# 3_-Digital_Input.net
KiCad netlist of a schematic drawn in Altium Designer
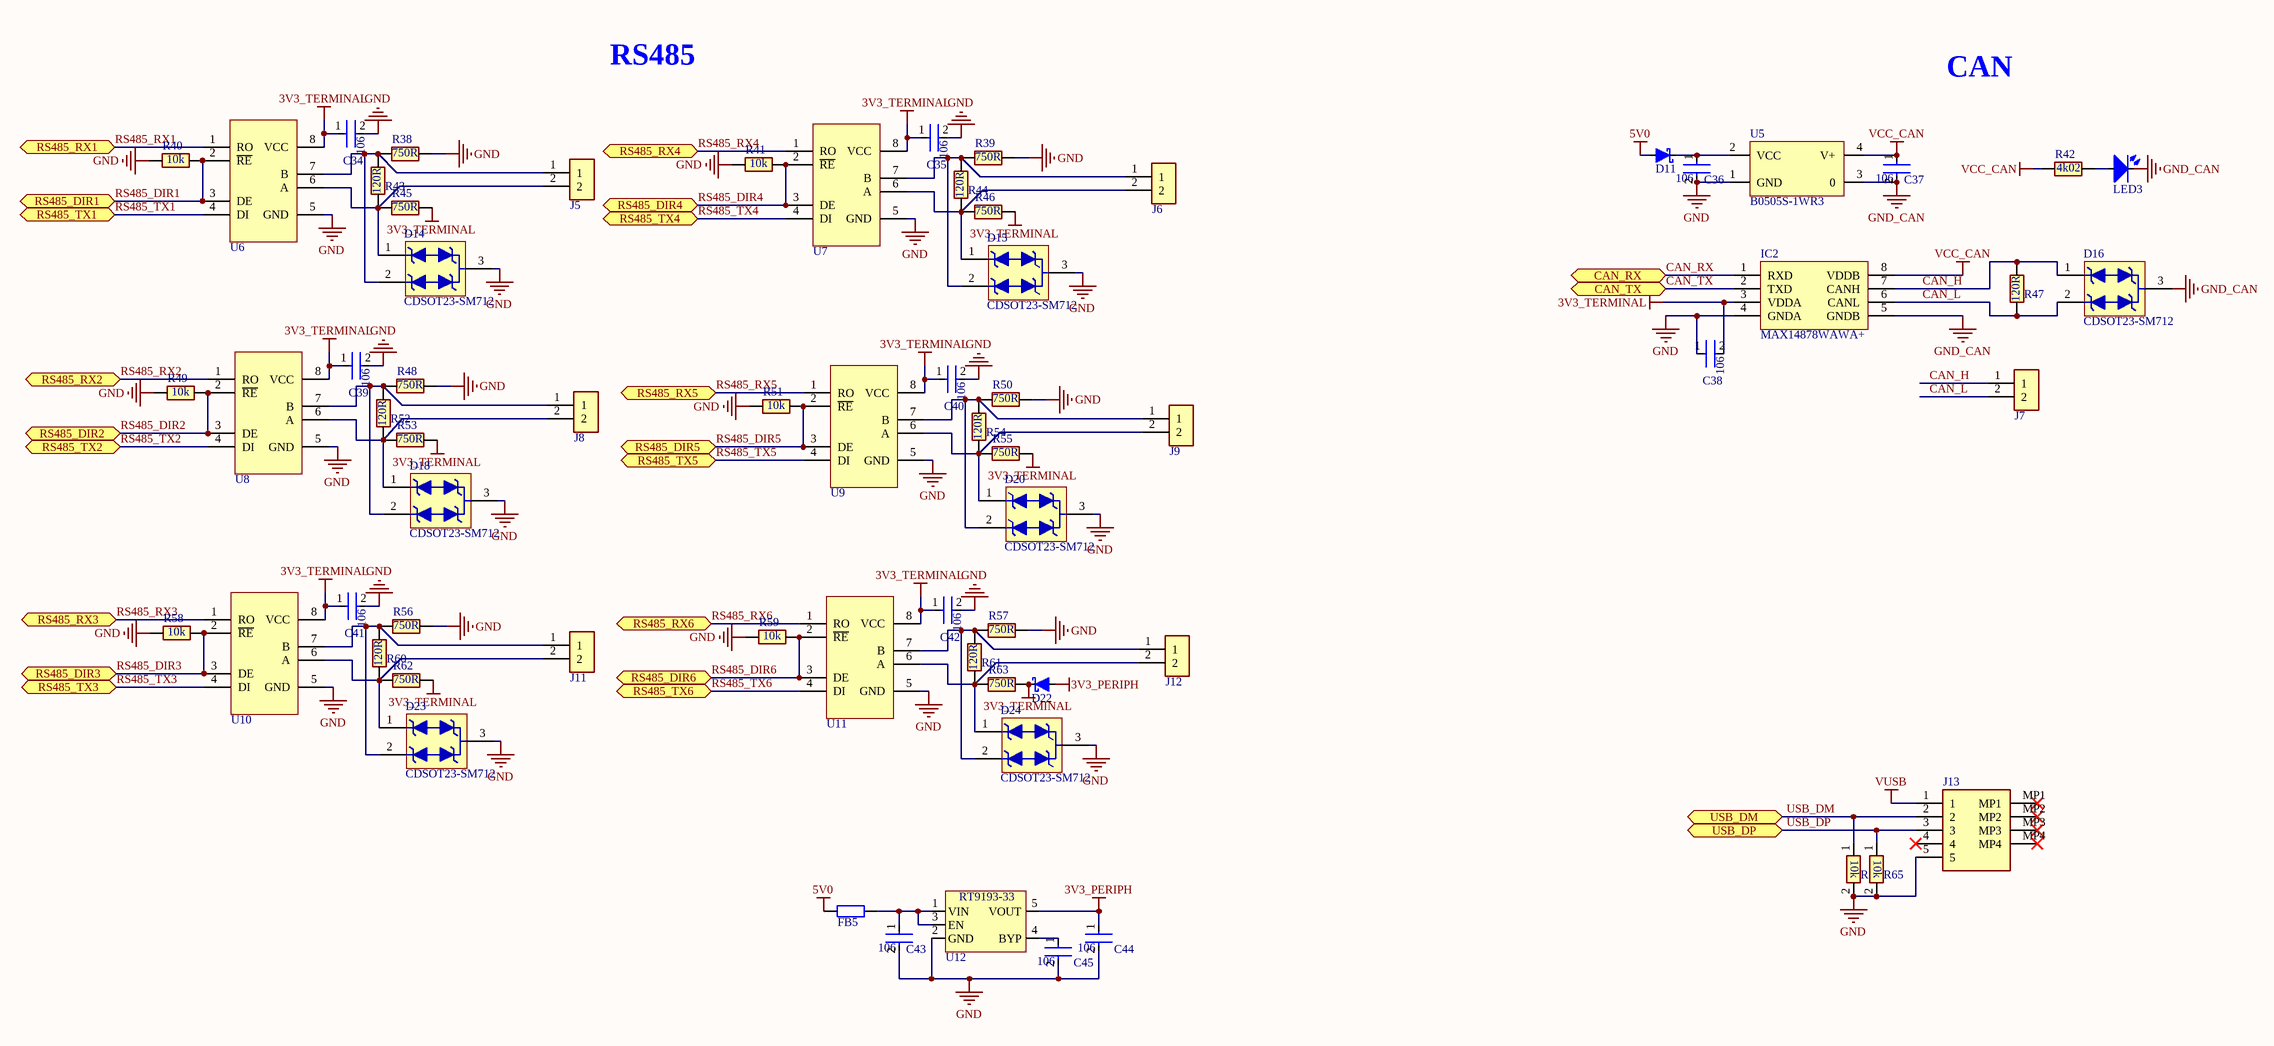
[diagram p0: [3]-Digital Input.SchDoc]

(export (version "E")
  (design (tool "Eeschema 10.0.6"))
  (components
    (comp (ref "C34")
      (value "C0603_106_35V")
      (footprint "SamacSys:C0603")
      (description "Multilayer Ceramic Capacitors MLCC - SMD/SMT 10 uF 35 VDC 20% 0603 X5R")
      (fields
        (field (name "MANUFACTURER_PART_NUMBER") "GRM188R6YA106MA73J")
        (field (name "MOUSER PART NUMBER") "81-GRM188R6YA106MA3J")
      )
      (libsource (lib "SamacSys") (part "C0603_106_35V"))
    )
    (comp (ref "C35")
      (value "C0603_106_35V")
      (footprint "SamacSys:C0603")
      (description "Multilayer Ceramic Capacitors MLCC - SMD/SMT 10 uF 35 VDC 20% 0603 X5R")
      (fields
        (field (name "MANUFACTURER_PART_NUMBER") "GRM188R6YA106MA73J")
        (field (name "MOUSER PART NUMBER") "81-GRM188R6YA106MA3J")
      )
      (libsource (lib "SamacSys") (part "C0603_106_35V"))
    )
    (comp (ref "C36")
      (value "C0603_106_35V")
      (footprint "SamacSys:C0603")
      (description "Multilayer Ceramic Capacitors MLCC - SMD/SMT 10 uF 35 VDC 20% 0603 X5R")
      (fields
        (field (name "MANUFACTURER_PART_NUMBER") "GRM188R6YA106MA73J")
        (field (name "MOUSER PART NUMBER") "81-GRM188R6YA106MA3J")
      )
      (libsource (lib "SamacSys") (part "C0603_106_35V"))
    )
    (comp (ref "C37")
      (value "C0603_106_35V")
      (footprint "SamacSys:C0603")
      (description "Multilayer Ceramic Capacitors MLCC - SMD/SMT 10 uF 35 VDC 20% 0603 X5R")
      (fields
        (field (name "MANUFACTURER_PART_NUMBER") "GRM188R6YA106MA73J")
        (field (name "MOUSER PART NUMBER") "81-GRM188R6YA106MA3J")
      )
      (libsource (lib "SamacSys") (part "C0603_106_35V"))
    )
    (comp (ref "C38")
      (value "C0603_106_35V")
      (footprint "SamacSys:C0603")
      (description "Multilayer Ceramic Capacitors MLCC - SMD/SMT 10 uF 35 VDC 20% 0603 X5R")
      (fields
        (field (name "MANUFACTURER_PART_NUMBER") "GRM188R6YA106MA73J")
        (field (name "MOUSER PART NUMBER") "81-GRM188R6YA106MA3J")
      )
      (libsource (lib "SamacSys") (part "C0603_106_35V"))
    )
    (comp (ref "C39")
      (value "C0603_106_35V")
      (footprint "SamacSys:C0603")
      (description "Multilayer Ceramic Capacitors MLCC - SMD/SMT 10 uF 35 VDC 20% 0603 X5R")
      (fields
        (field (name "MANUFACTURER_PART_NUMBER") "GRM188R6YA106MA73J")
        (field (name "MOUSER PART NUMBER") "81-GRM188R6YA106MA3J")
      )
      (libsource (lib "SamacSys") (part "C0603_106_35V"))
    )
    (comp (ref "C40")
      (value "C0603_106_35V")
      (footprint "SamacSys:C0603")
      (description "Multilayer Ceramic Capacitors MLCC - SMD/SMT 10 uF 35 VDC 20% 0603 X5R")
      (fields
        (field (name "MANUFACTURER_PART_NUMBER") "GRM188R6YA106MA73J")
        (field (name "MOUSER PART NUMBER") "81-GRM188R6YA106MA3J")
      )
      (libsource (lib "SamacSys") (part "C0603_106_35V"))
    )
    (comp (ref "C41")
      (value "C0603_106_35V")
      (footprint "SamacSys:C0603")
      (description "Multilayer Ceramic Capacitors MLCC - SMD/SMT 10 uF 35 VDC 20% 0603 X5R")
      (fields
        (field (name "MANUFACTURER_PART_NUMBER") "GRM188R6YA106MA73J")
        (field (name "MOUSER PART NUMBER") "81-GRM188R6YA106MA3J")
      )
      (libsource (lib "SamacSys") (part "C0603_106_35V"))
    )
    (comp (ref "C42")
      (value "C0603_106_35V")
      (footprint "SamacSys:C0603")
      (description "Multilayer Ceramic Capacitors MLCC - SMD/SMT 10 uF 35 VDC 20% 0603 X5R")
      (fields
        (field (name "MANUFACTURER_PART_NUMBER") "GRM188R6YA106MA73J")
        (field (name "MOUSER PART NUMBER") "81-GRM188R6YA106MA3J")
      )
      (libsource (lib "SamacSys") (part "C0603_106_35V"))
    )
    (comp (ref "C43")
      (value "C0603_106_35V")
      (footprint "SamacSys:C0603")
      (description "Multilayer Ceramic Capacitors MLCC - SMD/SMT 10 uF 35 VDC 20% 0603 X5R")
      (fields
        (field (name "MANUFACTURER_PART_NUMBER") "GRM188R6YA106MA73J")
        (field (name "MOUSER PART NUMBER") "81-GRM188R6YA106MA3J")
      )
      (libsource (lib "SamacSys") (part "C0603_106_35V"))
    )
    (comp (ref "C44")
      (value "C0603_106_35V")
      (footprint "SamacSys:C0603")
      (description "Multilayer Ceramic Capacitors MLCC - SMD/SMT 10 uF 35 VDC 20% 0603 X5R")
      (fields
        (field (name "MANUFACTURER_PART_NUMBER") "GRM188R6YA106MA73J")
        (field (name "MOUSER PART NUMBER") "81-GRM188R6YA106MA3J")
      )
      (libsource (lib "SamacSys") (part "C0603_106_35V"))
    )
    (comp (ref "C45")
      (value "C0603_106_35V")
      (footprint "SamacSys:C0603")
      (description "Multilayer Ceramic Capacitors MLCC - SMD/SMT 10 uF 35 VDC 20% 0603 X5R")
      (fields
        (field (name "MANUFACTURER_PART_NUMBER") "GRM188R6YA106MA73J")
        (field (name "MOUSER PART NUMBER") "81-GRM188R6YA106MA3J")
      )
      (libsource (lib "SamacSys") (part "C0603_106_35V"))
    )
    (comp (ref "D11")
      (value "PMEG40T30ERX")
      (footprint "SamacSys:SOD123")
      (description "Schottky Diode 40V 3A")
      (fields (field (name "MOUSER PART NUMBER") "771-PMEG40T30ERX"))
      (libsource (lib "SamacSys") (part "PMEG40T30ERX"))
    )
    (comp (ref "D14")
      (value "CDSOT23-SM712")
      (footprint "SamacSys:SOT-23")
      (fields (field (name "MANUFACTURER") "Bourns Inc."))
      (libsource (lib "SamacSys") (part "CDSOT23-SM712"))
    )
    (comp (ref "D15")
      (value "CDSOT23-SM712")
      (footprint "SamacSys:SOT-23")
      (fields (field (name "MANUFACTURER") "Bourns Inc."))
      (libsource (lib "SamacSys") (part "CDSOT23-SM712"))
    )
    (comp (ref "D16")
      (value "CDSOT23-SM712")
      (footprint "SamacSys:SOT-23")
      (fields (field (name "MANUFACTURER") "Bourns Inc."))
      (libsource (lib "SamacSys") (part "CDSOT23-SM712"))
    )
    (comp (ref "D18")
      (value "CDSOT23-SM712")
      (footprint "SamacSys:SOT-23")
      (fields (field (name "MANUFACTURER") "Bourns Inc."))
      (libsource (lib "SamacSys") (part "CDSOT23-SM712"))
    )
    (comp (ref "D20")
      (value "CDSOT23-SM712")
      (footprint "SamacSys:SOT-23")
      (fields (field (name "MANUFACTURER") "Bourns Inc."))
      (libsource (lib "SamacSys") (part "CDSOT23-SM712"))
    )
    (comp (ref "D22")
      (value "PMEG40T30ERX")
      (footprint "SamacSys:SOD123")
      (description "Schottky Diode 40V 3A")
      (fields (field (name "MOUSER PART NUMBER") "771-PMEG40T30ERX"))
      (libsource (lib "SamacSys") (part "PMEG40T30ERX"))
    )
    (comp (ref "D23")
      (value "CDSOT23-SM712")
      (footprint "SamacSys:SOT-23")
      (fields (field (name "MANUFACTURER") "Bourns Inc."))
      (libsource (lib "SamacSys") (part "CDSOT23-SM712"))
    )
    (comp (ref "D24")
      (value "CDSOT23-SM712")
      (footprint "SamacSys:SOT-23")
      (fields (field (name "MANUFACTURER") "Bourns Inc."))
      (libsource (lib "SamacSys") (part "CDSOT23-SM712"))
    )
    (comp (ref "FB5")
      (value "FERRIT_0805_1A")
      (footprint "SamacSys:FB0805")
      (fields
        (field (name "MANUFACTURER") "Laird-Signal Integrity Products")
        (field (name "PART NUMBER") "MI0805J102R-10")
      )
      (libsource (lib "SamacSys") (part "FERRIT_0805_1A"))
    )
    (comp (ref "IC2")
      (value "MAX14878WAWA+")
      (footprint "SamacSys:8-SOIC-W")
      (description "Integrated Circuit")
      (fields (field (name "MOUSER PART NUMBER") "700-MAX14878WAWA+"))
      (libsource (lib "SamacSys") (part "MAX14878WAWA+"))
    )
    (comp (ref "J5")
      (value "Terminal_2P_5.08mm")
      (footprint "SamacSys:1729128")
      (description "Fixed Terminal Blocks 2P 5.08mm 90DEG")
      (fields
        (field (name "MANUFACTURER_PART_NUMBER") "1729128")
        (field (name "MOUSER PART NUMBER") "651-1729128")
      )
      (libsource (lib "SamacSys") (part "Terminal_2P_5.08mm"))
    )
    (comp (ref "J6")
      (value "Terminal_2P_5.08mm")
      (footprint "SamacSys:1729128")
      (description "Fixed Terminal Blocks 2P 5.08mm 90DEG")
      (fields
        (field (name "MANUFACTURER_PART_NUMBER") "1729128")
        (field (name "MOUSER PART NUMBER") "651-1729128")
      )
      (libsource (lib "SamacSys") (part "Terminal_2P_5.08mm"))
    )
    (comp (ref "J7")
      (value "Terminal_2P_5.08mm")
      (footprint "SamacSys:1729128")
      (description "Fixed Terminal Blocks 2P 5.08mm 90DEG")
      (fields
        (field (name "MANUFACTURER_PART_NUMBER") "1729128")
        (field (name "MOUSER PART NUMBER") "651-1729128")
      )
      (libsource (lib "SamacSys") (part "Terminal_2P_5.08mm"))
    )
    (comp (ref "J8")
      (value "Terminal_2P_5.08mm")
      (footprint "SamacSys:1729128")
      (description "Fixed Terminal Blocks 2P 5.08mm 90DEG")
      (fields
        (field (name "MANUFACTURER_PART_NUMBER") "1729128")
        (field (name "MOUSER PART NUMBER") "651-1729128")
      )
      (libsource (lib "SamacSys") (part "Terminal_2P_5.08mm"))
    )
    (comp (ref "J9")
      (value "Terminal_2P_5.08mm")
      (footprint "SamacSys:1729128")
      (description "Fixed Terminal Blocks 2P 5.08mm 90DEG")
      (fields
        (field (name "MANUFACTURER_PART_NUMBER") "1729128")
        (field (name "MOUSER PART NUMBER") "651-1729128")
      )
      (libsource (lib "SamacSys") (part "Terminal_2P_5.08mm"))
    )
    (comp (ref "J11")
      (value "Terminal_2P_5.08mm")
      (footprint "SamacSys:1729128")
      (description "Fixed Terminal Blocks 2P 5.08mm 90DEG")
      (fields
        (field (name "MANUFACTURER_PART_NUMBER") "1729128")
        (field (name "MOUSER PART NUMBER") "651-1729128")
      )
      (libsource (lib "SamacSys") (part "Terminal_2P_5.08mm"))
    )
    (comp (ref "J12")
      (value "Terminal_2P_5.08mm")
      (footprint "SamacSys:1729128")
      (description "Fixed Terminal Blocks 2P 5.08mm 90DEG")
      (fields
        (field (name "MANUFACTURER_PART_NUMBER") "1729128")
        (field (name "MOUSER PART NUMBER") "651-1729128")
      )
      (libsource (lib "SamacSys") (part "Terminal_2P_5.08mm"))
    )
    (comp (ref "J13")
      (value "1734035-3")
      (footprint "17340353")
      (description "Connector")
      (fields (field (name "MOUSER PART NUMBER") "571-1734035-3"))
      (libsource (lib "SamacSys") (part "1734035-3"))
    )
    (comp (ref "LED3")
      (value "LED0603_Blue")
      (footprint "SamacSys:LED0603")
      (description "Blue 470nm LED Indication - Discrete 3.2V 0603 (1608 Metric)")
      (fields
        (field (name "MANUFACTURER_PART_NUMBER") "150060BS75000")
        (field (name "MOUSER PART NUMBER") "710-150060BS75000")
      )
      (libsource (lib "SamacSys") (part "LED0603_Blue"))
    )
    (comp (ref "R38")
      (value "R0603_750R")
      (footprint "SamacSys:RES-SMD-0603")
      (description "Resistor")
      (fields
        (field (name "MANUFACTURER_PART_NUMBER") "ERJ-3EKF7500V")
        (field (name "MOUSER PART NUMBER") "667-ERJ-3EKF7500V")
      )
      (libsource (lib "SamacSys") (part "R0603_750R"))
    )
    (comp (ref "R39")
      (value "R0603_750R")
      (footprint "SamacSys:RES-SMD-0603")
      (description "Resistor")
      (fields
        (field (name "MANUFACTURER_PART_NUMBER") "ERJ-3EKF7500V")
        (field (name "MOUSER PART NUMBER") "667-ERJ-3EKF7500V")
      )
      (libsource (lib "SamacSys") (part "R0603_750R"))
    )
    (comp (ref "R40")
      (value "R0603_10k")
      (footprint "SamacSys:RES-SMD-0603")
      (description "Thick Film Resistors - SMD 0603 10Kohms 1% AEC-Q200")
      (fields
        (field (name "MANUFACTURER_PART_NUMBER") "ERJ-3EKF1002V")
        (field (name "MOUSER PART NUMBER") "667-ERJ-3EKF1002V")
      )
      (libsource (lib "SamacSys") (part "R0603_10k"))
    )
    (comp (ref "R41")
      (value "R0603_10k")
      (footprint "SamacSys:RES-SMD-0603")
      (description "Thick Film Resistors - SMD 0603 10Kohms 1% AEC-Q200")
      (fields
        (field (name "MANUFACTURER_PART_NUMBER") "ERJ-3EKF1002V")
        (field (name "MOUSER PART NUMBER") "667-ERJ-3EKF1002V")
      )
      (libsource (lib "SamacSys") (part "R0603_10k"))
    )
    (comp (ref "R42")
      (value "R0603_4k02")
      (footprint "SamacSys:RES-SMD-0603")
      (description "Resistor")
      (fields
        (field (name "MANUFACTURER_PART_NUMBER") "ERJ-3EKF4021V")
        (field (name "MOUSER PART NUMBER") "667-ERJ-3EKF4021V")
      )
      (libsource (lib "SamacSys") (part "R0603_4k02"))
    )
    (comp (ref "R43")
      (value "R0603_120R")
      (footprint "SamacSys:RES-SMD-0603")
      (description "Thick Film Resistors - SMD 0603 120ohms 1% AEC-Q200")
      (fields
        (field (name "MANUFACTURER_PART_NUMBER") "ERJ-3EKF1200V")
        (field (name "MOUSER PART NUMBER") "667-ERJ-3EKF1200V")
      )
      (libsource (lib "SamacSys") (part "R0603_120R"))
    )
    (comp (ref "R44")
      (value "R0603_120R")
      (footprint "SamacSys:RES-SMD-0603")
      (description "Thick Film Resistors - SMD 0603 120ohms 1% AEC-Q200")
      (fields
        (field (name "MANUFACTURER_PART_NUMBER") "ERJ-3EKF1200V")
        (field (name "MOUSER PART NUMBER") "667-ERJ-3EKF1200V")
      )
      (libsource (lib "SamacSys") (part "R0603_120R"))
    )
    (comp (ref "R45")
      (value "R0603_750R")
      (footprint "SamacSys:RES-SMD-0603")
      (description "Resistor")
      (fields
        (field (name "MANUFACTURER_PART_NUMBER") "ERJ-3EKF7500V")
        (field (name "MOUSER PART NUMBER") "667-ERJ-3EKF7500V")
      )
      (libsource (lib "SamacSys") (part "R0603_750R"))
    )
    (comp (ref "R46")
      (value "R0603_750R")
      (footprint "SamacSys:RES-SMD-0603")
      (description "Resistor")
      (fields
        (field (name "MANUFACTURER_PART_NUMBER") "ERJ-3EKF7500V")
        (field (name "MOUSER PART NUMBER") "667-ERJ-3EKF7500V")
      )
      (libsource (lib "SamacSys") (part "R0603_750R"))
    )
    (comp (ref "R47")
      (value "R0603_120R")
      (footprint "SamacSys:RES-SMD-0603")
      (description "Thick Film Resistors - SMD 0603 120ohms 1% AEC-Q200")
      (fields
        (field (name "MANUFACTURER_PART_NUMBER") "ERJ-3EKF1200V")
        (field (name "MOUSER PART NUMBER") "667-ERJ-3EKF1200V")
      )
      (libsource (lib "SamacSys") (part "R0603_120R"))
    )
    (comp (ref "R48")
      (value "R0603_750R")
      (footprint "SamacSys:RES-SMD-0603")
      (description "Resistor")
      (fields
        (field (name "MANUFACTURER_PART_NUMBER") "ERJ-3EKF7500V")
        (field (name "MOUSER PART NUMBER") "667-ERJ-3EKF7500V")
      )
      (libsource (lib "SamacSys") (part "R0603_750R"))
    )
    (comp (ref "R49")
      (value "R0603_10k")
      (footprint "SamacSys:RES-SMD-0603")
      (description "Thick Film Resistors - SMD 0603 10Kohms 1% AEC-Q200")
      (fields
        (field (name "MANUFACTURER_PART_NUMBER") "ERJ-3EKF1002V")
        (field (name "MOUSER PART NUMBER") "667-ERJ-3EKF1002V")
      )
      (libsource (lib "SamacSys") (part "R0603_10k"))
    )
    (comp (ref "R50")
      (value "R0603_750R")
      (footprint "SamacSys:RES-SMD-0603")
      (description "Resistor")
      (fields
        (field (name "MANUFACTURER_PART_NUMBER") "ERJ-3EKF7500V")
        (field (name "MOUSER PART NUMBER") "667-ERJ-3EKF7500V")
      )
      (libsource (lib "SamacSys") (part "R0603_750R"))
    )
    (comp (ref "R51")
      (value "R0603_10k")
      (footprint "SamacSys:RES-SMD-0603")
      (description "Thick Film Resistors - SMD 0603 10Kohms 1% AEC-Q200")
      (fields
        (field (name "MANUFACTURER_PART_NUMBER") "ERJ-3EKF1002V")
        (field (name "MOUSER PART NUMBER") "667-ERJ-3EKF1002V")
      )
      (libsource (lib "SamacSys") (part "R0603_10k"))
    )
    (comp (ref "R52")
      (value "R0603_120R")
      (footprint "SamacSys:RES-SMD-0603")
      (description "Thick Film Resistors - SMD 0603 120ohms 1% AEC-Q200")
      (fields
        (field (name "MANUFACTURER_PART_NUMBER") "ERJ-3EKF1200V")
        (field (name "MOUSER PART NUMBER") "667-ERJ-3EKF1200V")
      )
      (libsource (lib "SamacSys") (part "R0603_120R"))
    )
    (comp (ref "R53")
      (value "R0603_750R")
      (footprint "SamacSys:RES-SMD-0603")
      (description "Resistor")
      (fields
        (field (name "MANUFACTURER_PART_NUMBER") "ERJ-3EKF7500V")
        (field (name "MOUSER PART NUMBER") "667-ERJ-3EKF7500V")
      )
      (libsource (lib "SamacSys") (part "R0603_750R"))
    )
    (comp (ref "R54")
      (value "R0603_120R")
      (footprint "SamacSys:RES-SMD-0603")
      (description "Thick Film Resistors - SMD 0603 120ohms 1% AEC-Q200")
      (fields
        (field (name "MANUFACTURER_PART_NUMBER") "ERJ-3EKF1200V")
        (field (name "MOUSER PART NUMBER") "667-ERJ-3EKF1200V")
      )
      (libsource (lib "SamacSys") (part "R0603_120R"))
    )
    (comp (ref "R55")
      (value "R0603_750R")
      (footprint "SamacSys:RES-SMD-0603")
      (description "Resistor")
      (fields
        (field (name "MANUFACTURER_PART_NUMBER") "ERJ-3EKF7500V")
        (field (name "MOUSER PART NUMBER") "667-ERJ-3EKF7500V")
      )
      (libsource (lib "SamacSys") (part "R0603_750R"))
    )
    (comp (ref "R56")
      (value "R0603_750R")
      (footprint "SamacSys:RES-SMD-0603")
      (description "Resistor")
      (fields
        (field (name "MANUFACTURER_PART_NUMBER") "ERJ-3EKF7500V")
        (field (name "MOUSER PART NUMBER") "667-ERJ-3EKF7500V")
      )
      (libsource (lib "SamacSys") (part "R0603_750R"))
    )
    (comp (ref "R57")
      (value "R0603_750R")
      (footprint "SamacSys:RES-SMD-0603")
      (description "Resistor")
      (fields
        (field (name "MANUFACTURER_PART_NUMBER") "ERJ-3EKF7500V")
        (field (name "MOUSER PART NUMBER") "667-ERJ-3EKF7500V")
      )
      (libsource (lib "SamacSys") (part "R0603_750R"))
    )
    (comp (ref "R58")
      (value "R0603_10k")
      (footprint "SamacSys:RES-SMD-0603")
      (description "Thick Film Resistors - SMD 0603 10Kohms 1% AEC-Q200")
      (fields
        (field (name "MANUFACTURER_PART_NUMBER") "ERJ-3EKF1002V")
        (field (name "MOUSER PART NUMBER") "667-ERJ-3EKF1002V")
      )
      (libsource (lib "SamacSys") (part "R0603_10k"))
    )
    (comp (ref "R59")
      (value "R0603_10k")
      (footprint "SamacSys:RES-SMD-0603")
      (description "Thick Film Resistors - SMD 0603 10Kohms 1% AEC-Q200")
      (fields
        (field (name "MANUFACTURER_PART_NUMBER") "ERJ-3EKF1002V")
        (field (name "MOUSER PART NUMBER") "667-ERJ-3EKF1002V")
      )
      (libsource (lib "SamacSys") (part "R0603_10k"))
    )
    (comp (ref "R60")
      (value "R0603_120R")
      (footprint "SamacSys:RES-SMD-0603")
      (description "Thick Film Resistors - SMD 0603 120ohms 1% AEC-Q200")
      (fields
        (field (name "MANUFACTURER_PART_NUMBER") "ERJ-3EKF1200V")
        (field (name "MOUSER PART NUMBER") "667-ERJ-3EKF1200V")
      )
      (libsource (lib "SamacSys") (part "R0603_120R"))
    )
    (comp (ref "R61")
      (value "R0603_120R")
      (footprint "SamacSys:RES-SMD-0603")
      (description "Thick Film Resistors - SMD 0603 120ohms 1% AEC-Q200")
      (fields
        (field (name "MANUFACTURER_PART_NUMBER") "ERJ-3EKF1200V")
        (field (name "MOUSER PART NUMBER") "667-ERJ-3EKF1200V")
      )
      (libsource (lib "SamacSys") (part "R0603_120R"))
    )
    (comp (ref "R62")
      (value "R0603_750R")
      (footprint "SamacSys:RES-SMD-0603")
      (description "Resistor")
      (fields
        (field (name "MANUFACTURER_PART_NUMBER") "ERJ-3EKF7500V")
        (field (name "MOUSER PART NUMBER") "667-ERJ-3EKF7500V")
      )
      (libsource (lib "SamacSys") (part "R0603_750R"))
    )
    (comp (ref "R63")
      (value "R0603_750R")
      (footprint "SamacSys:RES-SMD-0603")
      (description "Resistor")
      (fields
        (field (name "MANUFACTURER_PART_NUMBER") "ERJ-3EKF7500V")
        (field (name "MOUSER PART NUMBER") "667-ERJ-3EKF7500V")
      )
      (libsource (lib "SamacSys") (part "R0603_750R"))
    )
    (comp (ref "R64")
      (value "R0603_10k")
      (footprint "SamacSys:RES-SMD-0603")
      (description "Thick Film Resistors - SMD 0603 10Kohms 1% AEC-Q200")
      (fields
        (field (name "MANUFACTURER_PART_NUMBER") "ERJ-3EKF1002V")
        (field (name "MOUSER PART NUMBER") "667-ERJ-3EKF1002V")
      )
      (libsource (lib "") (part "R0603_10k_1"))
    )
    (comp (ref "R65")
      (value "R0603_10k")
      (footprint "SamacSys:RES-SMD-0603")
      (description "Thick Film Resistors - SMD 0603 10Kohms 1% AEC-Q200")
      (fields
        (field (name "MANUFACTURER_PART_NUMBER") "ERJ-3EKF1002V")
        (field (name "MOUSER PART NUMBER") "667-ERJ-3EKF1002V")
      )
      (libsource (lib "") (part "R0603_10k_1"))
    )
    (comp (ref "U5")
      (value "B0505S-1WR3")
      (footprint "SamacSys:B0505S-1WR3")
      (fields (field (name "MANUFACTURER") "Mornsun America, LLC"))
      (libsource (lib "SamacSys") (part "B0505S-1WR3"))
    )
    (comp (ref "U6")
      (value "MAX3485")
      (footprint "SamacSys:8-SOIC")
      (fields (field (name "MANUFACTURER") "Maxim Integrated") (field (name "PART NUMBER") "MAX3485EESA+"))
      (libsource (lib "SamacSys") (part "MAX3485"))
    )
    (comp (ref "U7")
      (value "MAX3485")
      (footprint "SamacSys:8-SOIC")
      (fields (field (name "MANUFACTURER") "Maxim Integrated") (field (name "PART NUMBER") "MAX3485EESA+"))
      (libsource (lib "SamacSys") (part "MAX3485"))
    )
    (comp (ref "U8")
      (value "MAX3485")
      (footprint "SamacSys:8-SOIC")
      (fields (field (name "MANUFACTURER") "Maxim Integrated") (field (name "PART NUMBER") "MAX3485EESA+"))
      (libsource (lib "SamacSys") (part "MAX3485"))
    )
    (comp (ref "U9")
      (value "MAX3485")
      (footprint "SamacSys:8-SOIC")
      (fields (field (name "MANUFACTURER") "Maxim Integrated") (field (name "PART NUMBER") "MAX3485EESA+"))
      (libsource (lib "SamacSys") (part "MAX3485"))
    )
    (comp (ref "U10")
      (value "MAX3485")
      (footprint "SamacSys:8-SOIC")
      (fields (field (name "MANUFACTURER") "Maxim Integrated") (field (name "PART NUMBER") "MAX3485EESA+"))
      (libsource (lib "SamacSys") (part "MAX3485"))
    )
    (comp (ref "U11")
      (value "MAX3485")
      (footprint "SamacSys:8-SOIC")
      (fields (field (name "MANUFACTURER") "Maxim Integrated") (field (name "PART NUMBER") "MAX3485EESA+"))
      (libsource (lib "SamacSys") (part "MAX3485"))
    )
    (comp (ref "U12")
      (value "RT9193-33GB")
      (footprint "SOT-23-5")
      (description "Linear Voltage Regulator IC Positive Fixed 1 Output 300mA SOT-23-5")
      (fields (field (name "MANUFACTURER") "Richtek USA Inc."))
      (libsource (lib "SamacSys") (part "RT9193-33GB"))
    )
  )
  (nets
    (net (code "1") (name "/CAN_H") (class "Default")
      (node (ref "D16") (pin "1") (pinfunction "1_1") (pintype "passive"))
      (node (ref "IC2") (pin "7") (pinfunction "CANH_7") (pintype "passive"))
      (node (ref "J7") (pin "1") (pinfunction "1_1") (pintype "passive"))
      (node (ref "R47") (pin "2") (pinfunction "2_2") (pintype "passive"))
    )
    (net (code "2") (name "/CAN_L") (class "Default")
      (node (ref "D16") (pin "2") (pinfunction "2_2") (pintype "passive"))
      (node (ref "IC2") (pin "6") (pinfunction "CANL_6") (pintype "passive"))
      (node (ref "J7") (pin "2") (pinfunction "2_2") (pintype "passive"))
      (node (ref "R47") (pin "1") (pinfunction "1_1") (pintype "passive"))
    )
    (net (code "3") (name "/CAN_RX") (class "Default")
      (node (ref "IC2") (pin "1") (pinfunction "RXD_1") (pintype "passive"))
    )
    (net (code "4") (name "/CAN_TX") (class "Default")
      (node (ref "IC2") (pin "2") (pinfunction "TXD_2") (pintype "passive"))
    )
    (net (code "5") (name "/RS485_DIR1") (class "Default")
      (node (ref "R40") (pin "2") (pinfunction "2_2") (pintype "passive"))
      (node (ref "U6") (pin "2") (pinfunction "~{RE}_2") (pintype "passive"))
      (node (ref "U6") (pin "3") (pinfunction "DE_3") (pintype "passive"))
    )
    (net (code "6") (name "/RS485_DIR2") (class "Default")
      (node (ref "R49") (pin "2") (pinfunction "2_2") (pintype "passive"))
      (node (ref "U8") (pin "2") (pinfunction "~{RE}_2") (pintype "passive"))
      (node (ref "U8") (pin "3") (pinfunction "DE_3") (pintype "passive"))
    )
    (net (code "7") (name "/RS485_DIR3") (class "Default")
      (node (ref "R58") (pin "2") (pinfunction "2_2") (pintype "passive"))
      (node (ref "U10") (pin "2") (pinfunction "~{RE}_2") (pintype "passive"))
      (node (ref "U10") (pin "3") (pinfunction "DE_3") (pintype "passive"))
    )
    (net (code "8") (name "/RS485_DIR4") (class "Default")
      (node (ref "R41") (pin "2") (pinfunction "2_2") (pintype "passive"))
      (node (ref "U7") (pin "2") (pinfunction "~{RE}_2") (pintype "passive"))
      (node (ref "U7") (pin "3") (pinfunction "DE_3") (pintype "passive"))
    )
    (net (code "9") (name "/RS485_DIR5") (class "Default")
      (node (ref "R51") (pin "2") (pinfunction "2_2") (pintype "passive"))
      (node (ref "U9") (pin "2") (pinfunction "~{RE}_2") (pintype "passive"))
      (node (ref "U9") (pin "3") (pinfunction "DE_3") (pintype "passive"))
    )
    (net (code "10") (name "/RS485_DIR6") (class "Default")
      (node (ref "R59") (pin "2") (pinfunction "2_2") (pintype "passive"))
      (node (ref "U11") (pin "2") (pinfunction "~{RE}_2") (pintype "passive"))
      (node (ref "U11") (pin "3") (pinfunction "DE_3") (pintype "passive"))
    )
    (net (code "11") (name "/RS485_RX1") (class "Default")
      (node (ref "U6") (pin "1") (pinfunction "RO_1") (pintype "passive"))
    )
    (net (code "12") (name "/RS485_RX2") (class "Default")
      (node (ref "U8") (pin "1") (pinfunction "RO_1") (pintype "passive"))
    )
    (net (code "13") (name "/RS485_RX3") (class "Default")
      (node (ref "U10") (pin "1") (pinfunction "RO_1") (pintype "passive"))
    )
    (net (code "14") (name "/RS485_RX4") (class "Default")
      (node (ref "U7") (pin "1") (pinfunction "RO_1") (pintype "passive"))
    )
    (net (code "15") (name "/RS485_RX5") (class "Default")
      (node (ref "U9") (pin "1") (pinfunction "RO_1") (pintype "passive"))
    )
    (net (code "16") (name "/RS485_RX6") (class "Default")
      (node (ref "U11") (pin "1") (pinfunction "RO_1") (pintype "passive"))
    )
    (net (code "17") (name "/RS485_TX1") (class "Default")
      (node (ref "U6") (pin "4") (pinfunction "DI_4") (pintype "passive"))
    )
    (net (code "18") (name "/RS485_TX2") (class "Default")
      (node (ref "U8") (pin "4") (pinfunction "DI_4") (pintype "passive"))
    )
    (net (code "19") (name "/RS485_TX3") (class "Default")
      (node (ref "U10") (pin "4") (pinfunction "DI_4") (pintype "passive"))
    )
    (net (code "20") (name "/RS485_TX4") (class "Default")
      (node (ref "U7") (pin "4") (pinfunction "DI_4") (pintype "passive"))
    )
    (net (code "21") (name "/RS485_TX5") (class "Default")
      (node (ref "U9") (pin "4") (pinfunction "DI_4") (pintype "passive"))
    )
    (net (code "22") (name "/RS485_TX6") (class "Default")
      (node (ref "U11") (pin "4") (pinfunction "DI_4") (pintype "passive"))
    )
    (net (code "23") (name "/USB_DM") (class "Default")
      (node (ref "J13") (pin "2") (pinfunction "2_2") (pintype "passive"))
      (node (ref "R64") (pin "1") (pinfunction "1_1") (pintype "passive"))
    )
    (net (code "24") (name "/USB_DP") (class "Default")
      (node (ref "J13") (pin "3") (pinfunction "3_3") (pintype "passive"))
      (node (ref "R65") (pin "1") (pinfunction "1_1") (pintype "passive"))
    )
    (net (code "25") (name "3V3_PERIPH") (class "Default")
      (node (ref "C44") (pin "1") (pinfunction "1_1") (pintype "passive"))
      (node (ref "D22") (pin "1") (pinfunction "A_1") (pintype "passive"))
      (node (ref "U12") (pin "5") (pinfunction "VOUT_5") (pintype "passive"))
    )
    (net (code "26") (name "3V3_TERMINAL") (class "Default")
      (node (ref "C34") (pin "1") (pinfunction "1_1") (pintype "passive"))
      (node (ref "C35") (pin "1") (pinfunction "1_1") (pintype "passive"))
      (node (ref "C38") (pin "2") (pinfunction "2_2") (pintype "passive"))
      (node (ref "C39") (pin "1") (pinfunction "1_1") (pintype "passive"))
      (node (ref "C40") (pin "1") (pinfunction "1_1") (pintype "passive"))
      (node (ref "C41") (pin "1") (pinfunction "1_1") (pintype "passive"))
      (node (ref "C42") (pin "1") (pinfunction "1_1") (pintype "passive"))
      (node (ref "D22") (pin "2") (pinfunction "K_2") (pintype "passive"))
      (node (ref "IC2") (pin "3") (pinfunction "VDDA_3") (pintype "passive"))
      (node (ref "R45") (pin "2") (pinfunction "2_2") (pintype "passive"))
      (node (ref "R46") (pin "2") (pinfunction "2_2") (pintype "passive"))
      (node (ref "R53") (pin "2") (pinfunction "2_2") (pintype "passive"))
      (node (ref "R55") (pin "2") (pinfunction "2_2") (pintype "passive"))
      (node (ref "R62") (pin "2") (pinfunction "2_2") (pintype "passive"))
      (node (ref "R63") (pin "2") (pinfunction "2_2") (pintype "passive"))
      (node (ref "U10") (pin "8") (pinfunction "VCC_8") (pintype "passive"))
      (node (ref "U11") (pin "8") (pinfunction "VCC_8") (pintype "passive"))
      (node (ref "U6") (pin "8") (pinfunction "VCC_8") (pintype "passive"))
      (node (ref "U7") (pin "8") (pinfunction "VCC_8") (pintype "passive"))
      (node (ref "U8") (pin "8") (pinfunction "VCC_8") (pintype "passive"))
      (node (ref "U9") (pin "8") (pinfunction "VCC_8") (pintype "passive"))
    )
    (net (code "27") (name "5V0") (class "Default")
      (node (ref "D11") (pin "1") (pinfunction "A_1") (pintype "passive"))
      (node (ref "FB5") (pin "1") (pinfunction "1_1") (pintype "passive"))
    )
    (net (code "28") (name "GND") (class "Default")
      (node (ref "C34") (pin "2") (pinfunction "2_2") (pintype "passive"))
      (node (ref "C35") (pin "2") (pinfunction "2_2") (pintype "passive"))
      (node (ref "C36") (pin "2") (pinfunction "2_2") (pintype "passive"))
      (node (ref "C38") (pin "1") (pinfunction "1_1") (pintype "passive"))
      (node (ref "C39") (pin "2") (pinfunction "2_2") (pintype "passive"))
      (node (ref "C40") (pin "2") (pinfunction "2_2") (pintype "passive"))
      (node (ref "C41") (pin "2") (pinfunction "2_2") (pintype "passive"))
      (node (ref "C42") (pin "2") (pinfunction "2_2") (pintype "passive"))
      (node (ref "C43") (pin "2") (pinfunction "2_2") (pintype "passive"))
      (node (ref "C44") (pin "2") (pinfunction "2_2") (pintype "passive"))
      (node (ref "C45") (pin "2") (pinfunction "2_2") (pintype "passive"))
      (node (ref "D14") (pin "3") (pinfunction "3_3") (pintype "passive"))
      (node (ref "D15") (pin "3") (pinfunction "3_3") (pintype "passive"))
      (node (ref "D18") (pin "3") (pinfunction "3_3") (pintype "passive"))
      (node (ref "D20") (pin "3") (pinfunction "3_3") (pintype "passive"))
      (node (ref "D23") (pin "3") (pinfunction "3_3") (pintype "passive"))
      (node (ref "D24") (pin "3") (pinfunction "3_3") (pintype "passive"))
      (node (ref "IC2") (pin "4") (pinfunction "GNDA_4") (pintype "passive"))
      (node (ref "J13") (pin "5") (pinfunction "5_5") (pintype "passive"))
      (node (ref "R38") (pin "2") (pinfunction "2_2") (pintype "passive"))
      (node (ref "R39") (pin "2") (pinfunction "2_2") (pintype "passive"))
      (node (ref "R40") (pin "1") (pinfunction "1_1") (pintype "passive"))
      (node (ref "R41") (pin "1") (pinfunction "1_1") (pintype "passive"))
      (node (ref "R48") (pin "2") (pinfunction "2_2") (pintype "passive"))
      (node (ref "R49") (pin "1") (pinfunction "1_1") (pintype "passive"))
      (node (ref "R50") (pin "2") (pinfunction "2_2") (pintype "passive"))
      (node (ref "R51") (pin "1") (pinfunction "1_1") (pintype "passive"))
      (node (ref "R56") (pin "2") (pinfunction "2_2") (pintype "passive"))
      (node (ref "R57") (pin "2") (pinfunction "2_2") (pintype "passive"))
      (node (ref "R58") (pin "1") (pinfunction "1_1") (pintype "passive"))
      (node (ref "R59") (pin "1") (pinfunction "1_1") (pintype "passive"))
      (node (ref "R64") (pin "2") (pinfunction "2_2") (pintype "passive"))
      (node (ref "R65") (pin "2") (pinfunction "2_2") (pintype "passive"))
      (node (ref "U10") (pin "5") (pinfunction "GND_5") (pintype "passive"))
      (node (ref "U11") (pin "5") (pinfunction "GND_5") (pintype "passive"))
      (node (ref "U12") (pin "2") (pinfunction "GND_2") (pintype "passive"))
      (node (ref "U5") (pin "1") (pinfunction "GND_1") (pintype "passive"))
      (node (ref "U6") (pin "5") (pinfunction "GND_5") (pintype "passive"))
      (node (ref "U7") (pin "5") (pinfunction "GND_5") (pintype "passive"))
      (node (ref "U8") (pin "5") (pinfunction "GND_5") (pintype "passive"))
      (node (ref "U9") (pin "5") (pinfunction "GND_5") (pintype "passive"))
    )
    (net (code "29") (name "GND_CAN") (class "Default")
      (node (ref "C37") (pin "2") (pinfunction "2_2") (pintype "passive"))
      (node (ref "D16") (pin "3") (pinfunction "3_3") (pintype "passive"))
      (node (ref "IC2") (pin "5") (pinfunction "GNDB_5") (pintype "passive"))
      (node (ref "LED3") (pin "1") (pinfunction "K_1") (pintype "passive"))
      (node (ref "U5") (pin "3") (pinfunction "0_3") (pintype "passive"))
    )
    (net (code "30") (name "Net-(D11-K)") (class "Default")
      (node (ref "C36") (pin "1") (pinfunction "1_1") (pintype "passive"))
      (node (ref "D11") (pin "2") (pinfunction "K_2") (pintype "passive"))
      (node (ref "U5") (pin "2") (pinfunction "VCC_2") (pintype "passive"))
    )
    (net (code "31") (name "Net-(LED3-A)") (class "Default")
      (node (ref "LED3") (pin "2") (pinfunction "A_2") (pintype "passive"))
      (node (ref "R42") (pin "2") (pinfunction "2_2") (pintype "passive"))
    )
    (net (code "32") (name "Net-(U6-A)") (class "Default")
      (node (ref "D14") (pin "1") (pinfunction "1_1") (pintype "passive"))
      (node (ref "J5") (pin "2") (pinfunction "2_2") (pintype "passive"))
      (node (ref "R43") (pin "1") (pinfunction "1_1") (pintype "passive"))
      (node (ref "R45") (pin "1") (pinfunction "1_1") (pintype "passive"))
      (node (ref "U6") (pin "6") (pinfunction "A_6") (pintype "passive"))
    )
    (net (code "33") (name "Net-(U6-B)") (class "Default")
      (node (ref "D14") (pin "2") (pinfunction "2_2") (pintype "passive"))
      (node (ref "J5") (pin "1") (pinfunction "1_1") (pintype "passive"))
      (node (ref "R38") (pin "1") (pinfunction "1_1") (pintype "passive"))
      (node (ref "R43") (pin "2") (pinfunction "2_2") (pintype "passive"))
      (node (ref "U6") (pin "7") (pinfunction "B_7") (pintype "passive"))
    )
    (net (code "34") (name "Net-(U7-A)") (class "Default")
      (node (ref "D15") (pin "1") (pinfunction "1_1") (pintype "passive"))
      (node (ref "J6") (pin "2") (pinfunction "2_2") (pintype "passive"))
      (node (ref "R44") (pin "1") (pinfunction "1_1") (pintype "passive"))
      (node (ref "R46") (pin "1") (pinfunction "1_1") (pintype "passive"))
      (node (ref "U7") (pin "6") (pinfunction "A_6") (pintype "passive"))
    )
    (net (code "35") (name "Net-(U7-B)") (class "Default")
      (node (ref "D15") (pin "2") (pinfunction "2_2") (pintype "passive"))
      (node (ref "J6") (pin "1") (pinfunction "1_1") (pintype "passive"))
      (node (ref "R39") (pin "1") (pinfunction "1_1") (pintype "passive"))
      (node (ref "R44") (pin "2") (pinfunction "2_2") (pintype "passive"))
      (node (ref "U7") (pin "7") (pinfunction "B_7") (pintype "passive"))
    )
    (net (code "36") (name "Net-(U8-A)") (class "Default")
      (node (ref "D18") (pin "1") (pinfunction "1_1") (pintype "passive"))
      (node (ref "J8") (pin "2") (pinfunction "2_2") (pintype "passive"))
      (node (ref "R52") (pin "1") (pinfunction "1_1") (pintype "passive"))
      (node (ref "R53") (pin "1") (pinfunction "1_1") (pintype "passive"))
      (node (ref "U8") (pin "6") (pinfunction "A_6") (pintype "passive"))
    )
    (net (code "37") (name "Net-(U8-B)") (class "Default")
      (node (ref "D18") (pin "2") (pinfunction "2_2") (pintype "passive"))
      (node (ref "J8") (pin "1") (pinfunction "1_1") (pintype "passive"))
      (node (ref "R48") (pin "1") (pinfunction "1_1") (pintype "passive"))
      (node (ref "R52") (pin "2") (pinfunction "2_2") (pintype "passive"))
      (node (ref "U8") (pin "7") (pinfunction "B_7") (pintype "passive"))
    )
    (net (code "38") (name "Net-(U9-A)") (class "Default")
      (node (ref "D20") (pin "1") (pinfunction "1_1") (pintype "passive"))
      (node (ref "J9") (pin "2") (pinfunction "2_2") (pintype "passive"))
      (node (ref "R54") (pin "1") (pinfunction "1_1") (pintype "passive"))
      (node (ref "R55") (pin "1") (pinfunction "1_1") (pintype "passive"))
      (node (ref "U9") (pin "6") (pinfunction "A_6") (pintype "passive"))
    )
    (net (code "39") (name "Net-(U9-B)") (class "Default")
      (node (ref "D20") (pin "2") (pinfunction "2_2") (pintype "passive"))
      (node (ref "J9") (pin "1") (pinfunction "1_1") (pintype "passive"))
      (node (ref "R50") (pin "1") (pinfunction "1_1") (pintype "passive"))
      (node (ref "R54") (pin "2") (pinfunction "2_2") (pintype "passive"))
      (node (ref "U9") (pin "7") (pinfunction "B_7") (pintype "passive"))
    )
    (net (code "40") (name "Net-(U10-A)") (class "Default")
      (node (ref "D23") (pin "1") (pinfunction "1_1") (pintype "passive"))
      (node (ref "J11") (pin "2") (pinfunction "2_2") (pintype "passive"))
      (node (ref "R60") (pin "1") (pinfunction "1_1") (pintype "passive"))
      (node (ref "R62") (pin "1") (pinfunction "1_1") (pintype "passive"))
      (node (ref "U10") (pin "6") (pinfunction "A_6") (pintype "passive"))
    )
    (net (code "41") (name "Net-(U10-B)") (class "Default")
      (node (ref "D23") (pin "2") (pinfunction "2_2") (pintype "passive"))
      (node (ref "J11") (pin "1") (pinfunction "1_1") (pintype "passive"))
      (node (ref "R56") (pin "1") (pinfunction "1_1") (pintype "passive"))
      (node (ref "R60") (pin "2") (pinfunction "2_2") (pintype "passive"))
      (node (ref "U10") (pin "7") (pinfunction "B_7") (pintype "passive"))
    )
    (net (code "42") (name "Net-(U11-A)") (class "Default")
      (node (ref "D24") (pin "1") (pinfunction "1_1") (pintype "passive"))
      (node (ref "J12") (pin "2") (pinfunction "2_2") (pintype "passive"))
      (node (ref "R61") (pin "1") (pinfunction "1_1") (pintype "passive"))
      (node (ref "R63") (pin "1") (pinfunction "1_1") (pintype "passive"))
      (node (ref "U11") (pin "6") (pinfunction "A_6") (pintype "passive"))
    )
    (net (code "43") (name "Net-(U11-B)") (class "Default")
      (node (ref "D24") (pin "2") (pinfunction "2_2") (pintype "passive"))
      (node (ref "J12") (pin "1") (pinfunction "1_1") (pintype "passive"))
      (node (ref "R57") (pin "1") (pinfunction "1_1") (pintype "passive"))
      (node (ref "R61") (pin "2") (pinfunction "2_2") (pintype "passive"))
      (node (ref "U11") (pin "7") (pinfunction "B_7") (pintype "passive"))
    )
    (net (code "44") (name "Net-(U12-BYP)") (class "Default")
      (node (ref "C45") (pin "1") (pinfunction "1_1") (pintype "passive"))
      (node (ref "U12") (pin "4") (pinfunction "BYP_4") (pintype "passive"))
    )
    (net (code "45") (name "Net-(U12-EN)") (class "Default")
      (node (ref "C43") (pin "1") (pinfunction "1_1") (pintype "passive"))
      (node (ref "FB5") (pin "2") (pinfunction "2_2") (pintype "passive"))
      (node (ref "U12") (pin "1") (pinfunction "VIN_1") (pintype "passive"))
      (node (ref "U12") (pin "3") (pinfunction "EN_3") (pintype "passive"))
    )
    (net (code "46") (name "VCC_CAN") (class "Default")
      (node (ref "C37") (pin "1") (pinfunction "1_1") (pintype "passive"))
      (node (ref "IC2") (pin "8") (pinfunction "VDDB_8") (pintype "passive"))
      (node (ref "R42") (pin "1") (pinfunction "1_1") (pintype "passive"))
      (node (ref "U5") (pin "4") (pinfunction "V+_4") (pintype "passive"))
    )
    (net (code "47") (name "VUSB") (class "Default")
      (node (ref "J13") (pin "1") (pinfunction "1_1") (pintype "passive"))
    )
    (net (code "48") (name "unconnected-(J13-Pad4)") (class "Default")
      (node (ref "J13") (pin "4") (pinfunction "4_4") (pintype "passive+no_connect"))
    )
    (net (code "49") (name "unconnected-(J13-PadMP1)") (class "Default")
      (node (ref "J13") (pin "MP1") (pinfunction "MP1_MP1") (pintype "passive+no_connect"))
    )
    (net (code "50") (name "unconnected-(J13-PadMP2)") (class "Default")
      (node (ref "J13") (pin "MP2") (pinfunction "MP2_MP2") (pintype "passive+no_connect"))
    )
    (net (code "51") (name "unconnected-(J13-PadMP3)") (class "Default")
      (node (ref "J13") (pin "MP3") (pinfunction "MP3_MP3") (pintype "passive+no_connect"))
    )
    (net (code "52") (name "unconnected-(J13-PadMP4)") (class "Default")
      (node (ref "J13") (pin "MP4") (pinfunction "MP4_MP4") (pintype "passive+no_connect"))
    )
  )
)
